# F3-Octo-Brushed-SIDE-USB-JMPR.net
KiCad netlist of a schematic drawn in EAGLE
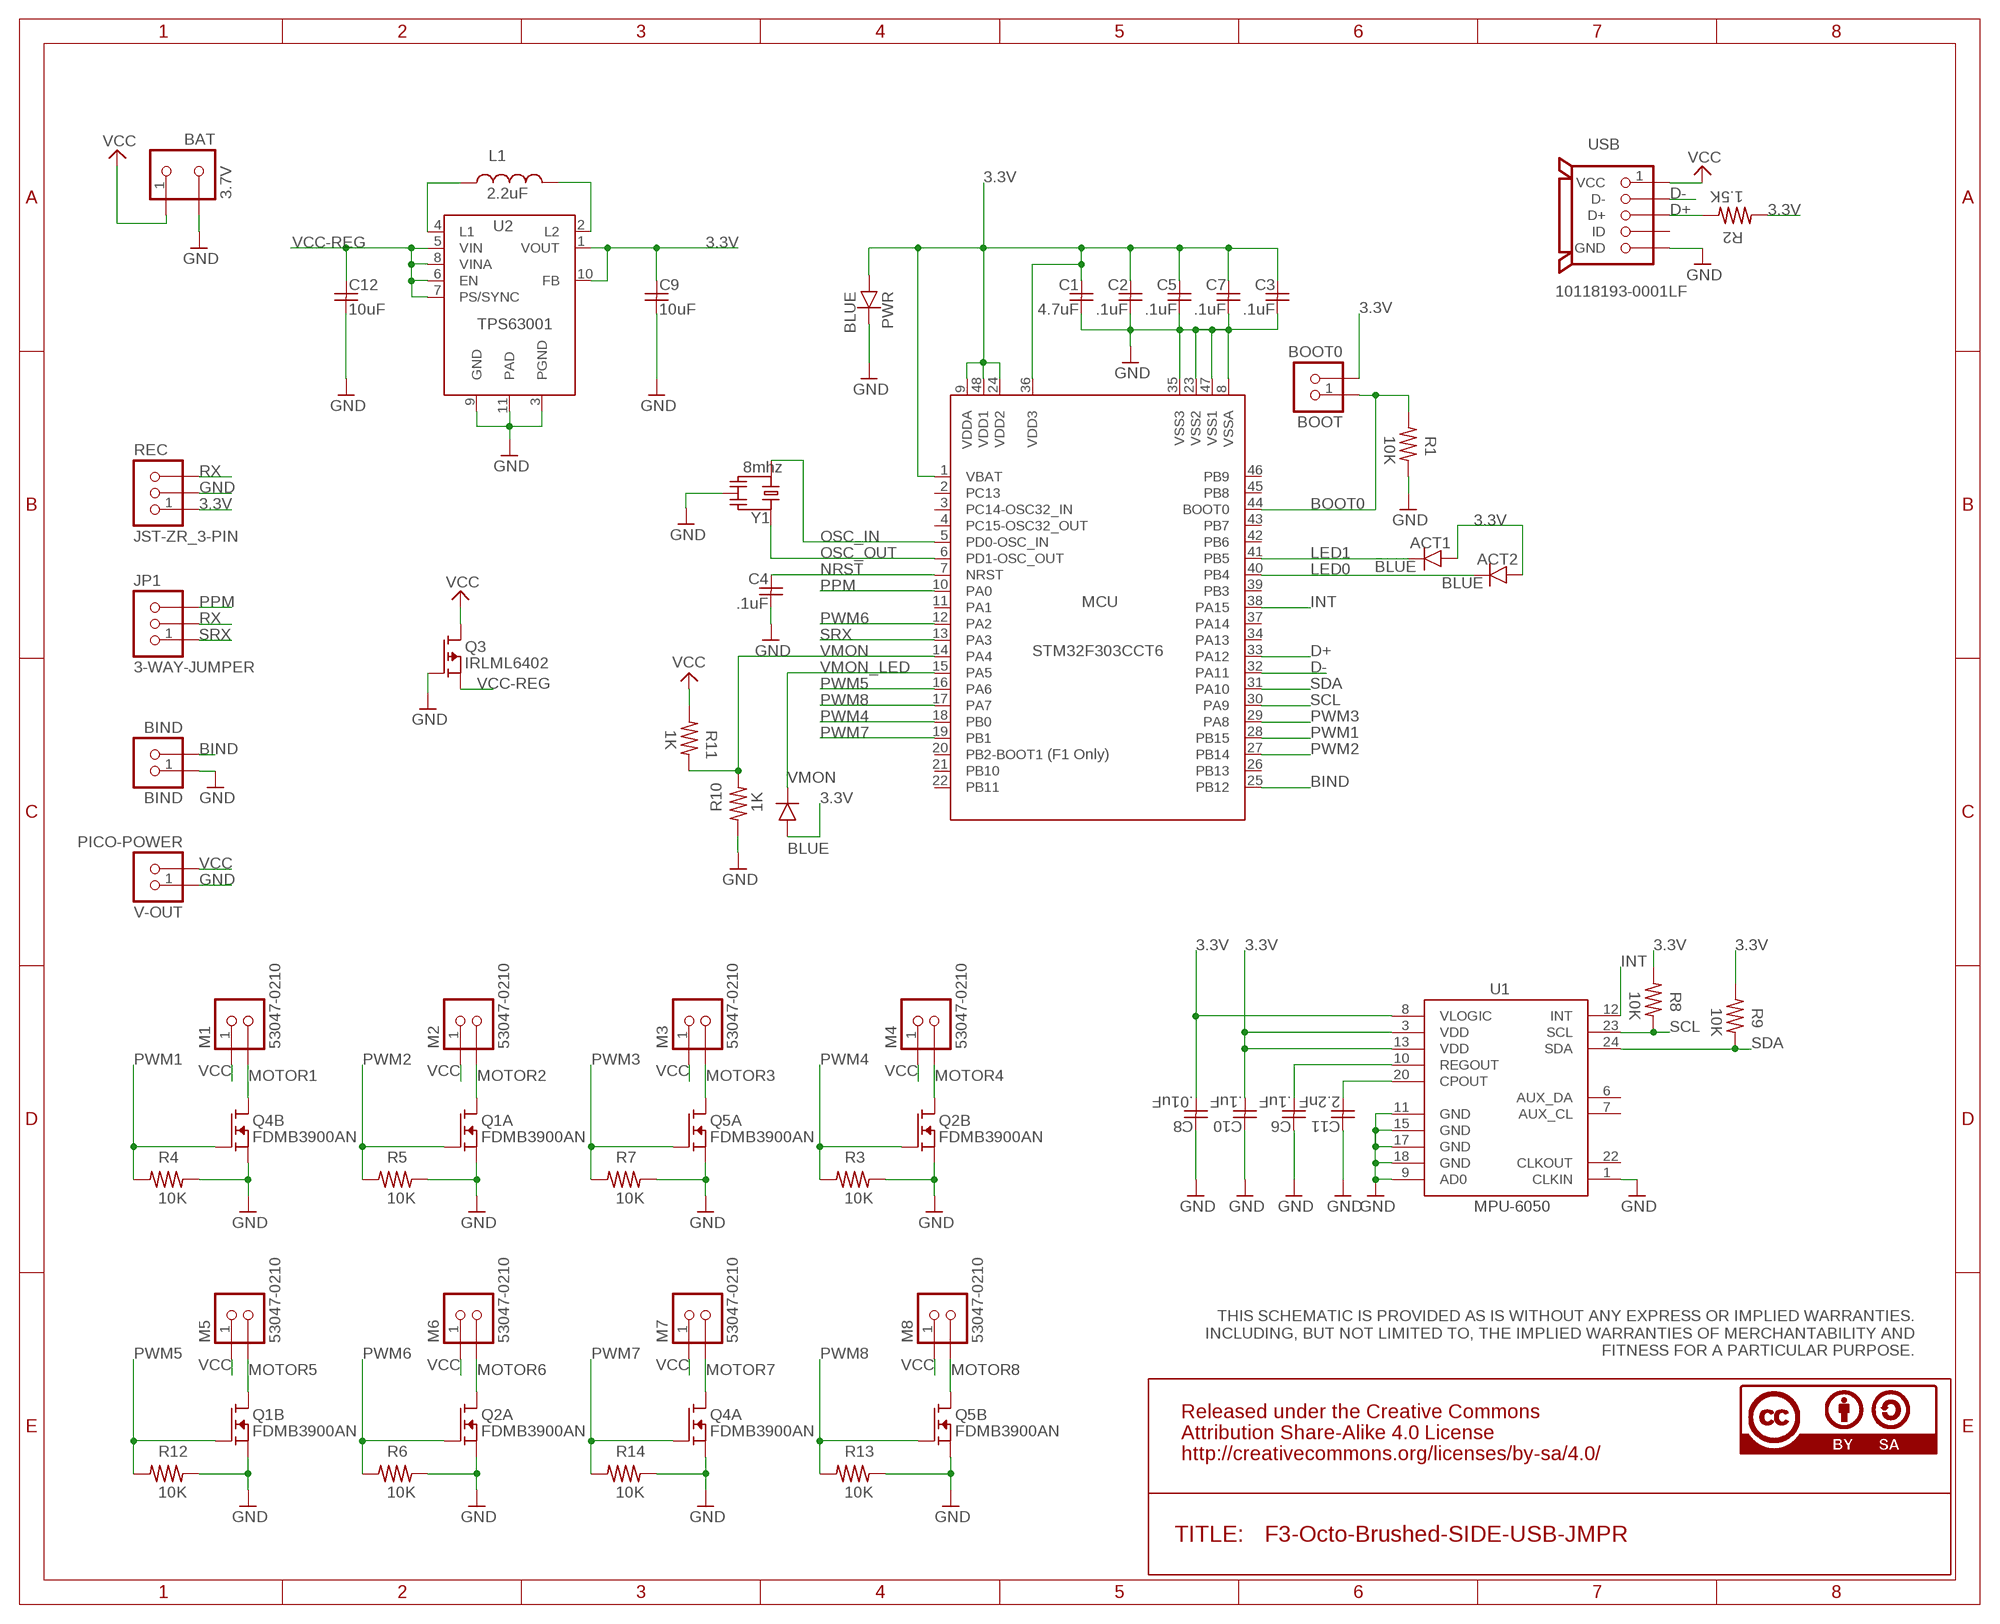
[diagram p0: schematic, sheet 1]

(export (version "E")
  (design (tool "Eeschema 10.0.6"))
  (components
    (comp (ref "ACT1")
      (value "BLUE")
      (footprint "eagle-import:SMD-CHIP-LED-0805")
      (fields (field (name "MF") "Kingbright") (field (name "MPN") "APHCM2012QBC/D-F01"))
      (libsource (lib "eagle-import") (part "SMD-CHIP-LED-0805"))
    )
    (comp (ref "ACT2")
      (value "BLUE")
      (footprint "eagle-import:SMD-CHIP-LED-0805")
      (fields (field (name "MF") "Kingbright") (field (name "MPN") "APHCM2012QBC/D-F01"))
      (libsource (lib "eagle-import") (part "SMD-CHIP-LED-0805"))
    )
    (comp (ref "BAT")
      (value "3.7V")
      (footprint "eagle-import:S2B-PH-K-S")
      (fields (field (name "MF") "JST") (field (name "MPN") "S2B-PH-K-S"))
      (libsource (lib "eagle-import") (part "JST-PH-BAT"))
    )
    (comp (ref "BIND")
      (value "BIND")
      (footprint "eagle-import:1.27MM-PINHEADX2")
      (fields (field (name "MF") "Sullins") (field (name "MPN") "GRPB021VWVN-RC (JUMPER IS M50-1930005)"))
      (libsource (lib "eagle-import") (part "1.27MM-PINHEADX2"))
    )
    (comp (ref "BOOT")
      (value "BOOT0")
      (footprint "eagle-import:1.27MM-PINHEADX2")
      (fields (field (name "MF") "Sullins") (field (name "MPN") "GRPB021VWVN-RC (JUMPER IS M50-1930005)"))
      (libsource (lib "eagle-import") (part "1.27MM-PINHEADX2"))
    )
    (comp (ref "C1")
      (value "4.7uF")
      (footprint "eagle-import:MUR-CAP-0603")
      (fields (field (name "MF") "Murata") (field (name "MPN") "GRJ188C70J475KE11D"))
      (libsource (lib "eagle-import") (part "CAPACITOR4.7UF"))
    )
    (comp (ref "C2")
      (value ".1uF")
      (footprint "eagle-import:MUR-CAP-0603")
      (fields (field (name "MF") "Murata") (field (name "MPN") "GRM188R71C104KA01D"))
      (libsource (lib "eagle-import") (part "CAPACITOR.1UF"))
    )
    (comp (ref "C3")
      (value ".1uF")
      (footprint "eagle-import:MUR-CAP-0603")
      (fields (field (name "MF") "Murata") (field (name "MPN") "GRM188R71C104KA01D"))
      (libsource (lib "eagle-import") (part "CAPACITOR.1UF"))
    )
    (comp (ref "C4")
      (value ".1uF")
      (footprint "eagle-import:MUR-CAP-0603")
      (fields (field (name "MF") "Murata") (field (name "MPN") "GRM188R71C104KA01D"))
      (libsource (lib "eagle-import") (part "CAPACITOR.1UF"))
    )
    (comp (ref "C5")
      (value ".1uF")
      (footprint "eagle-import:MUR-CAP-0603")
      (fields (field (name "MF") "Murata") (field (name "MPN") "GRM188R71C104KA01D"))
      (libsource (lib "eagle-import") (part "CAPACITOR.1UF"))
    )
    (comp (ref "C6")
      (value ".1uF")
      (footprint "eagle-import:MUR-CAP-0603")
      (fields (field (name "MF") "Murata") (field (name "MPN") "GRM188R71C104KA01D"))
      (libsource (lib "eagle-import") (part "CAPACITOR.1UF"))
    )
    (comp (ref "C7")
      (value ".1uF")
      (footprint "eagle-import:MUR-CAP-0603")
      (fields (field (name "MF") "Murata") (field (name "MPN") "GRM188R71C104KA01D"))
      (libsource (lib "eagle-import") (part "CAPACITOR.1UF"))
    )
    (comp (ref "C8")
      (value ".01uF")
      (footprint "eagle-import:MUR-CAP-0603")
      (fields (field (name "MF") "Murata") (field (name "MPN") "GRM188R71C103KA01D"))
      (libsource (lib "eagle-import") (part "CAPACITOR.01UF"))
    )
    (comp (ref "C9")
      (value "10uF")
      (footprint "eagle-import:YUDEN-CAP-0805")
      (fields (field (name "MF") "Taiyo Yuden") (field (name "MPN") "JMK212AB7106KG-T"))
      (libsource (lib "eagle-import") (part "CAPACITOR10UF"))
    )
    (comp (ref "C10")
      (value ".1uF")
      (footprint "eagle-import:MUR-CAP-0603")
      (fields (field (name "MF") "Murata") (field (name "MPN") "GRM188R71C104KA01D"))
      (libsource (lib "eagle-import") (part "CAPACITOR.1UF"))
    )
    (comp (ref "C11")
      (value "2.2nF")
      (footprint "eagle-import:MUR-CAP-0603")
      (fields (field (name "MF") "Murata") (field (name "MPN") "GRM188R71C222KA01D"))
      (libsource (lib "eagle-import") (part "CAPACITOR2.2NF"))
    )
    (comp (ref "C12")
      (value "10uF")
      (footprint "eagle-import:YUDEN-CAP-0805")
      (fields (field (name "MF") "Taiyo Yuden") (field (name "MPN") "JMK212AB7106KG-T"))
      (libsource (lib "eagle-import") (part "CAPACITOR10UF"))
    )
    (comp (ref "JP1")
      (value "3-WAY-JUMPER")
      (footprint "eagle-import:3-WAY-JUMPER")
      (libsource (lib "eagle-import") (part "3-WAY-JUMPER"))
    )
    (comp (ref "L1")
      (value "2.2uF")
      (footprint "eagle-import:NR301X")
      (fields (field (name "MF") "Taiyo Yuden") (field (name "MPN") "NR3015T2R2M"))
      (libsource (lib "eagle-import") (part "NR301X"))
    )
    (comp (ref "M1")
      (value "53047-0210")
      (footprint "eagle-import:PICO-53047-02")
      (fields (field (name "MF") "MOLEX"))
      (libsource (lib "eagle-import") (part "PICO-1.25-MOTOR"))
    )
    (comp (ref "M2")
      (value "53047-0210")
      (footprint "eagle-import:PICO-53047-02")
      (fields (field (name "MF") "MOLEX"))
      (libsource (lib "eagle-import") (part "PICO-1.25-MOTOR"))
    )
    (comp (ref "M3")
      (value "53047-0210")
      (footprint "eagle-import:PICO-53047-02")
      (fields (field (name "MF") "MOLEX"))
      (libsource (lib "eagle-import") (part "PICO-1.25-MOTOR"))
    )
    (comp (ref "M4")
      (value "53047-0210")
      (footprint "eagle-import:PICO-53047-02")
      (fields (field (name "MF") "MOLEX"))
      (libsource (lib "eagle-import") (part "PICO-1.25-MOTOR"))
    )
    (comp (ref "M5")
      (value "53047-0210")
      (footprint "eagle-import:PICO-53047-02")
      (fields (field (name "MF") "MOLEX"))
      (libsource (lib "eagle-import") (part "PICO-1.25-MOTOR"))
    )
    (comp (ref "M6")
      (value "53047-0210")
      (footprint "eagle-import:PICO-53047-02")
      (fields (field (name "MF") "MOLEX"))
      (libsource (lib "eagle-import") (part "PICO-1.25-MOTOR"))
    )
    (comp (ref "M7")
      (value "53047-0210")
      (footprint "eagle-import:PICO-53047-02")
      (fields (field (name "MF") "MOLEX"))
      (libsource (lib "eagle-import") (part "PICO-1.25-MOTOR"))
    )
    (comp (ref "M8")
      (value "53047-0210")
      (footprint "eagle-import:PICO-53047-02")
      (fields (field (name "MF") "MOLEX"))
      (libsource (lib "eagle-import") (part "PICO-1.25-MOTOR"))
    )
    (comp (ref "MCU")
      (value "STM32F303CCT6")
      (footprint "eagle-import:LQFP48-7X7")
      (fields (field (name "MF") "ST"))
      (libsource (lib "eagle-import") (part "STM32FX03-F3"))
    )
    (comp (ref "PWR")
      (value "BLUE")
      (footprint "eagle-import:SMD-CHIP-LED-0805")
      (fields (field (name "MF") "Kingbright") (field (name "MPN") "APHCM2012QBC/D-F01"))
      (libsource (lib "eagle-import") (part "SMD-CHIP-LED-0805"))
    )
    (comp (ref "Q1")
      (value "FDMB3900AN")
      (footprint "eagle-import:8-WDFN-DUAL")
      (fields (field (name "MF") "Fairchild"))
      (libsource (lib "eagle-import") (part "FDMB3900AN"))
    )
    (comp (ref "Q2")
      (value "FDMB3900AN")
      (footprint "eagle-import:8-WDFN-DUAL")
      (fields (field (name "MF") "Fairchild"))
      (libsource (lib "eagle-import") (part "FDMB3900AN"))
    )
    (comp (ref "Q3")
      (value "IRLML6402")
      (footprint "eagle-import:SOT-23")
      (fields (field (name "MF") "IR"))
      (libsource (lib "eagle-import") (part "IRLML6402"))
    )
    (comp (ref "Q4")
      (value "FDMB3900AN")
      (footprint "eagle-import:8-WDFN-DUAL")
      (fields (field (name "MF") "Fairchild"))
      (libsource (lib "eagle-import") (part "FDMB3900AN"))
    )
    (comp (ref "Q5")
      (value "FDMB3900AN")
      (footprint "eagle-import:8-WDFN-DUAL")
      (fields (field (name "MF") "Fairchild"))
      (libsource (lib "eagle-import") (part "FDMB3900AN"))
    )
    (comp (ref "R1")
      (value "10K")
      (footprint "eagle-import:VISH-RES-0603")
      (fields (field (name "MF") "Vishay") (field (name "MPN") "CRCW060310K0FKEAHP"))
      (libsource (lib "eagle-import") (part "RESISTOR10K"))
    )
    (comp (ref "R2")
      (value "1.5K")
      (footprint "eagle-import:VISH-RES-0603")
      (fields (field (name "MF") "Vishay") (field (name "MPN") "CRCW06031K50FKEAHP"))
      (libsource (lib "eagle-import") (part "RESISTOR1.5K"))
    )
    (comp (ref "R3")
      (value "10K")
      (footprint "eagle-import:VISH-RES-0603")
      (fields (field (name "MF") "Vishay") (field (name "MPN") "CRCW060310K0FKEAHP"))
      (libsource (lib "eagle-import") (part "RESISTOR10K"))
    )
    (comp (ref "R4")
      (value "10K")
      (footprint "eagle-import:VISH-RES-0603")
      (fields (field (name "MF") "Vishay") (field (name "MPN") "CRCW060310K0FKEAHP"))
      (libsource (lib "eagle-import") (part "RESISTOR10K"))
    )
    (comp (ref "R5")
      (value "10K")
      (footprint "eagle-import:VISH-RES-0603")
      (fields (field (name "MF") "Vishay") (field (name "MPN") "CRCW060310K0FKEAHP"))
      (libsource (lib "eagle-import") (part "RESISTOR10K"))
    )
    (comp (ref "R6")
      (value "10K")
      (footprint "eagle-import:VISH-RES-0603")
      (fields (field (name "MF") "Vishay") (field (name "MPN") "CRCW060310K0FKEAHP"))
      (libsource (lib "eagle-import") (part "RESISTOR10K"))
    )
    (comp (ref "R7")
      (value "10K")
      (footprint "eagle-import:VISH-RES-0603")
      (fields (field (name "MF") "Vishay") (field (name "MPN") "CRCW060310K0FKEAHP"))
      (libsource (lib "eagle-import") (part "RESISTOR10K"))
    )
    (comp (ref "R8")
      (value "10K")
      (footprint "eagle-import:VISH-RES-0603")
      (fields (field (name "MF") "Vishay") (field (name "MPN") "CRCW060310K0FKEAHP"))
      (libsource (lib "eagle-import") (part "RESISTOR10K"))
    )
    (comp (ref "R9")
      (value "10K")
      (footprint "eagle-import:VISH-RES-0603")
      (fields (field (name "MF") "Vishay") (field (name "MPN") "CRCW060310K0FKEAHP"))
      (libsource (lib "eagle-import") (part "RESISTOR10K"))
    )
    (comp (ref "R10")
      (value "1K")
      (footprint "eagle-import:VISH-RES-0603")
      (fields (field (name "MF") "Vishay") (field (name "MPN") "CRCW06031K00FKEAHP"))
      (libsource (lib "eagle-import") (part "RESISTOR1K"))
    )
    (comp (ref "R11")
      (value "1K")
      (footprint "eagle-import:VISH-RES-0603")
      (fields (field (name "MF") "Vishay") (field (name "MPN") "CRCW06031K00FKEAHP"))
      (libsource (lib "eagle-import") (part "RESISTOR1K"))
    )
    (comp (ref "R12")
      (value "10K")
      (footprint "eagle-import:VISH-RES-0603")
      (fields (field (name "MF") "Vishay") (field (name "MPN") "CRCW060310K0FKEAHP"))
      (libsource (lib "eagle-import") (part "RESISTOR10K"))
    )
    (comp (ref "R13")
      (value "10K")
      (footprint "eagle-import:VISH-RES-0603")
      (fields (field (name "MF") "Vishay") (field (name "MPN") "CRCW060310K0FKEAHP"))
      (libsource (lib "eagle-import") (part "RESISTOR10K"))
    )
    (comp (ref "R14")
      (value "10K")
      (footprint "eagle-import:VISH-RES-0603")
      (fields (field (name "MF") "Vishay") (field (name "MPN") "CRCW060310K0FKEAHP"))
      (libsource (lib "eagle-import") (part "RESISTOR10K"))
    )
    (comp (ref "REC")
      (value "JST-ZR_3-PIN")
      (footprint "eagle-import:S3B-ZR")
      (fields (field (name "MF") "JST") (field (name "MPN") "S3B-ZR"))
      (libsource (lib "eagle-import") (part "JST-ZR_3-PIN"))
    )
    (comp (ref "U1")
      (value "MPU-6050")
      (footprint "eagle-import:QFN24-4X4")
      (fields (field (name "MF") "Invensense"))
      (libsource (lib "eagle-import") (part "MPU-6050"))
    )
    (comp (ref "U2")
      (value "TPS63001")
      (footprint "eagle-import:VSON-N10")
      (fields (field (name "MF") "TI") (field (name "MPN") "TPS63001DRCR"))
      (libsource (lib "eagle-import") (part "TPS630XX-TPS63001"))
    )
    (comp (ref "USB")
      (value "10118193-0001LF")
      (footprint "eagle-import:10118193-0001LF")
      (fields (field (name "MF") "FCI"))
      (libsource (lib "eagle-import") (part "USB-MICRO-B-FCI"))
    )
    (comp (ref "V-OUT")
      (value "PICO-POWER")
      (footprint "eagle-import:PICO_1.25_.5MM")
      (fields (field (name "MF") "Molex") (field (name "MPN") "53047-0210"))
      (libsource (lib "eagle-import") (part "PICO-POWER"))
    )
    (comp (ref "VMON")
      (value "BLUE")
      (footprint "eagle-import:SMD-CHIP-LED-0805")
      (fields (field (name "MF") "Kingbright") (field (name "MPN") "APHCM2012QBC/D-F01"))
      (libsource (lib "eagle-import") (part "SMD-CHIP-LED-0805"))
    )
    (comp (ref "Y1")
      (value "8mhz")
      (footprint "eagle-import:RESONATOR_8")
      (fields (field (name "MF") "Murata") (field (name "MPN") "CSTCE8M00G55-R0"))
      (libsource (lib "eagle-import") (part "RESONATOR8MHZ"))
    )
  )
  (nets
    (net (code "1") (name "/3.3V") (class "Default")
      (node (ref "ACT1") (pin "A") (pinfunction "A_A") (pintype "passive"))
      (node (ref "ACT2") (pin "A") (pinfunction "A_A") (pintype "passive"))
      (node (ref "BOOT") (pin "2") (pinfunction "2_2") (pintype "passive"))
      (node (ref "C1") (pin "1") (pinfunction "1_1") (pintype "passive"))
      (node (ref "C10") (pin "2") (pinfunction "2_2") (pintype "passive"))
      (node (ref "C2") (pin "1") (pinfunction "1_1") (pintype "passive"))
      (node (ref "C3") (pin "1") (pinfunction "1_1") (pintype "passive"))
      (node (ref "C5") (pin "1") (pinfunction "1_1") (pintype "passive"))
      (node (ref "C7") (pin "1") (pinfunction "1_1") (pintype "passive"))
      (node (ref "C8") (pin "2") (pinfunction "2_2") (pintype "passive"))
      (node (ref "C9") (pin "1") (pinfunction "1_1") (pintype "passive"))
      (node (ref "MCU") (pin "1") (pinfunction "VBAT_1") (pintype "bidirectional"))
      (node (ref "MCU") (pin "24") (pinfunction "VDD2_24") (pintype "bidirectional"))
      (node (ref "MCU") (pin "36") (pinfunction "VDD3_36") (pintype "bidirectional"))
      (node (ref "MCU") (pin "48") (pinfunction "VDD1_48") (pintype "bidirectional"))
      (node (ref "MCU") (pin "9") (pinfunction "VDDA_9") (pintype "bidirectional"))
      (node (ref "PWR") (pin "A") (pinfunction "A_A") (pintype "passive"))
      (node (ref "R2") (pin "2") (pinfunction "2_2") (pintype "passive"))
      (node (ref "R8") (pin "2") (pinfunction "2_2") (pintype "passive"))
      (node (ref "R9") (pin "2") (pinfunction "2_2") (pintype "passive"))
      (node (ref "REC") (pin "1") (pinfunction "1_1") (pintype "bidirectional"))
      (node (ref "U1") (pin "13") (pinfunction "VDD_13") (pintype "bidirectional"))
      (node (ref "U1") (pin "3") (pinfunction "VDD_3") (pintype "bidirectional"))
      (node (ref "U1") (pin "8") (pinfunction "VLOGIC_8") (pintype "bidirectional"))
      (node (ref "U2") (pin "1") (pinfunction "VOUT_1") (pintype "bidirectional"))
      (node (ref "U2") (pin "10") (pinfunction "FB_10") (pintype "bidirectional"))
      (node (ref "VMON") (pin "A") (pinfunction "A_A") (pintype "passive"))
    )
    (net (code "2") (name "/BIND") (class "Default")
      (node (ref "BIND") (pin "2") (pinfunction "2_2") (pintype "passive"))
      (node (ref "MCU") (pin "25") (pinfunction "PB12_25") (pintype "bidirectional"))
    )
    (net (code "3") (name "/BOOT0") (class "Default")
      (node (ref "BOOT") (pin "1") (pinfunction "1_1") (pintype "passive"))
      (node (ref "MCU") (pin "44") (pinfunction "BOOT0_44") (pintype "bidirectional"))
      (node (ref "R1") (pin "2") (pinfunction "2_2") (pintype "passive"))
    )
    (net (code "4") (name "/D+") (class "Default")
      (node (ref "MCU") (pin "33") (pinfunction "PA12_33") (pintype "bidirectional"))
      (node (ref "R2") (pin "1") (pinfunction "1_1") (pintype "passive"))
      (node (ref "USB") (pin "3") (pinfunction "D+_3") (pintype "passive"))
    )
    (net (code "5") (name "/D-") (class "Default")
      (node (ref "MCU") (pin "32") (pinfunction "PA11_32") (pintype "bidirectional"))
      (node (ref "USB") (pin "2") (pinfunction "D-_2") (pintype "passive"))
    )
    (net (code "6") (name "/INT") (class "Default")
      (node (ref "MCU") (pin "38") (pinfunction "PA15_38") (pintype "bidirectional"))
      (node (ref "U1") (pin "12") (pinfunction "INT_12") (pintype "bidirectional"))
    )
    (net (code "7") (name "/LED0") (class "Default")
      (node (ref "ACT2") (pin "C") (pinfunction "C_C") (pintype "passive"))
      (node (ref "MCU") (pin "40") (pinfunction "PB4_40") (pintype "bidirectional"))
    )
    (net (code "8") (name "/LED1") (class "Default")
      (node (ref "ACT1") (pin "C") (pinfunction "C_C") (pintype "passive"))
      (node (ref "MCU") (pin "41") (pinfunction "PB5_41") (pintype "bidirectional"))
    )
    (net (code "9") (name "/MOTOR1") (class "Default")
      (node (ref "M1") (pin "2") (pinfunction "2_2") (pintype "passive"))
      (node (ref "Q4") (pin "5+6") (pinfunction "D_5+6") (pintype "bidirectional"))
    )
    (net (code "10") (name "/MOTOR2") (class "Default")
      (node (ref "M2") (pin "2") (pinfunction "2_2") (pintype "passive"))
      (node (ref "Q1") (pin "7+8") (pinfunction "D_7+8") (pintype "bidirectional"))
    )
    (net (code "11") (name "/MOTOR3") (class "Default")
      (node (ref "M3") (pin "2") (pinfunction "2_2") (pintype "passive"))
      (node (ref "Q5") (pin "7+8") (pinfunction "D_7+8") (pintype "bidirectional"))
    )
    (net (code "12") (name "/MOTOR4") (class "Default")
      (node (ref "M4") (pin "2") (pinfunction "2_2") (pintype "passive"))
      (node (ref "Q2") (pin "5+6") (pinfunction "D_5+6") (pintype "bidirectional"))
    )
    (net (code "13") (name "/MOTOR5") (class "Default")
      (node (ref "M5") (pin "2") (pinfunction "2_2") (pintype "passive"))
      (node (ref "Q1") (pin "5+6") (pinfunction "D_5+6") (pintype "bidirectional"))
    )
    (net (code "14") (name "/MOTOR6") (class "Default")
      (node (ref "M6") (pin "2") (pinfunction "2_2") (pintype "passive"))
      (node (ref "Q2") (pin "7+8") (pinfunction "D_7+8") (pintype "bidirectional"))
    )
    (net (code "15") (name "/MOTOR7") (class "Default")
      (node (ref "M7") (pin "2") (pinfunction "2_2") (pintype "passive"))
      (node (ref "Q4") (pin "7+8") (pinfunction "D_7+8") (pintype "bidirectional"))
    )
    (net (code "16") (name "/MOTOR8") (class "Default")
      (node (ref "M8") (pin "2") (pinfunction "2_2") (pintype "passive"))
      (node (ref "Q5") (pin "5+6") (pinfunction "D_5+6") (pintype "bidirectional"))
    )
    (net (code "17") (name "/NRST") (class "Default")
      (node (ref "C4") (pin "1") (pinfunction "1_1") (pintype "passive"))
      (node (ref "MCU") (pin "7") (pinfunction "NRST_7") (pintype "bidirectional"))
    )
    (net (code "18") (name "/OSC_IN") (class "Default")
      (node (ref "MCU") (pin "5") (pinfunction "PD0-OSC_IN_5") (pintype "bidirectional"))
      (node (ref "Y1") (pin "3") (pinfunction "3_3") (pintype "passive"))
    )
    (net (code "19") (name "/OSC_OUT") (class "Default")
      (node (ref "MCU") (pin "6") (pinfunction "PD1-OSC_OUT_6") (pintype "bidirectional"))
      (node (ref "Y1") (pin "1") (pinfunction "1_1") (pintype "passive"))
    )
    (net (code "20") (name "/PPM") (class "Default")
      (node (ref "JP1") (pin "3") (pinfunction "3_3") (pintype "bidirectional"))
      (node (ref "MCU") (pin "10") (pinfunction "PA0_10") (pintype "bidirectional"))
    )
    (net (code "21") (name "/PWM1") (class "Default")
      (node (ref "MCU") (pin "28") (pinfunction "PB15_28") (pintype "bidirectional"))
      (node (ref "Q4") (pin "4@G2") (pinfunction "G_4@G2") (pintype "bidirectional"))
      (node (ref "R4") (pin "2") (pinfunction "2_2") (pintype "passive"))
    )
    (net (code "22") (name "/PWM2") (class "Default")
      (node (ref "MCU") (pin "27") (pinfunction "PB14_27") (pintype "bidirectional"))
      (node (ref "Q1") (pin "2@G1") (pinfunction "G_2@G1") (pintype "bidirectional"))
      (node (ref "R5") (pin "2") (pinfunction "2_2") (pintype "passive"))
    )
    (net (code "23") (name "/PWM3") (class "Default")
      (node (ref "MCU") (pin "29") (pinfunction "PA8_29") (pintype "bidirectional"))
      (node (ref "Q5") (pin "2@G1") (pinfunction "G_2@G1") (pintype "bidirectional"))
      (node (ref "R7") (pin "2") (pinfunction "2_2") (pintype "passive"))
    )
    (net (code "24") (name "/PWM4") (class "Default")
      (node (ref "MCU") (pin "18") (pinfunction "PB0_18") (pintype "bidirectional"))
      (node (ref "Q2") (pin "4@G2") (pinfunction "G_4@G2") (pintype "bidirectional"))
      (node (ref "R3") (pin "2") (pinfunction "2_2") (pintype "passive"))
    )
    (net (code "25") (name "/PWM5") (class "Default")
      (node (ref "MCU") (pin "16") (pinfunction "PA6_16") (pintype "bidirectional"))
      (node (ref "Q1") (pin "4@G2") (pinfunction "G_4@G2") (pintype "bidirectional"))
      (node (ref "R12") (pin "2") (pinfunction "2_2") (pintype "passive"))
    )
    (net (code "26") (name "/PWM6") (class "Default")
      (node (ref "MCU") (pin "12") (pinfunction "PA2_12") (pintype "bidirectional"))
      (node (ref "Q2") (pin "2@G1") (pinfunction "G_2@G1") (pintype "bidirectional"))
      (node (ref "R6") (pin "2") (pinfunction "2_2") (pintype "passive"))
    )
    (net (code "27") (name "/PWM7") (class "Default")
      (node (ref "MCU") (pin "19") (pinfunction "PB1_19") (pintype "bidirectional"))
      (node (ref "Q4") (pin "2@G1") (pinfunction "G_2@G1") (pintype "bidirectional"))
      (node (ref "R14") (pin "2") (pinfunction "2_2") (pintype "passive"))
    )
    (net (code "28") (name "/PWM8") (class "Default")
      (node (ref "MCU") (pin "17") (pinfunction "PA7_17") (pintype "bidirectional"))
      (node (ref "Q5") (pin "4@G2") (pinfunction "G_4@G2") (pintype "bidirectional"))
      (node (ref "R13") (pin "2") (pinfunction "2_2") (pintype "passive"))
    )
    (net (code "29") (name "/RX") (class "Default")
      (node (ref "JP1") (pin "2") (pinfunction "2_2") (pintype "bidirectional"))
      (node (ref "REC") (pin "3") (pinfunction "3_3") (pintype "bidirectional"))
    )
    (net (code "30") (name "/SCL") (class "Default")
      (node (ref "MCU") (pin "30") (pinfunction "PA9_30") (pintype "bidirectional"))
      (node (ref "R8") (pin "1") (pinfunction "1_1") (pintype "passive"))
      (node (ref "U1") (pin "23") (pinfunction "SCL_23") (pintype "bidirectional"))
    )
    (net (code "31") (name "/SDA") (class "Default")
      (node (ref "MCU") (pin "31") (pinfunction "PA10_31") (pintype "bidirectional"))
      (node (ref "R9") (pin "1") (pinfunction "1_1") (pintype "passive"))
      (node (ref "U1") (pin "24") (pinfunction "SDA_24") (pintype "bidirectional"))
    )
    (net (code "32") (name "/SRX") (class "Default")
      (node (ref "JP1") (pin "1") (pinfunction "1_1") (pintype "bidirectional"))
      (node (ref "MCU") (pin "13") (pinfunction "PA3_13") (pintype "bidirectional"))
    )
    (net (code "33") (name "/VCC-REG") (class "Default")
      (node (ref "C12") (pin "1") (pinfunction "1_1") (pintype "passive"))
      (node (ref "Q3") (pin "2") (pinfunction "S_2") (pintype "bidirectional"))
      (node (ref "U2") (pin "5") (pinfunction "VIN_5") (pintype "bidirectional"))
      (node (ref "U2") (pin "6") (pinfunction "EN_6") (pintype "bidirectional"))
      (node (ref "U2") (pin "7") (pinfunction "PS/SYNC_7") (pintype "bidirectional"))
      (node (ref "U2") (pin "8") (pinfunction "VINA_8") (pintype "bidirectional"))
    )
    (net (code "34") (name "/VMON") (class "Default")
      (node (ref "MCU") (pin "14") (pinfunction "PA4_14") (pintype "bidirectional"))
      (node (ref "R10") (pin "1") (pinfunction "1_1") (pintype "passive"))
      (node (ref "R11") (pin "1") (pinfunction "1_1") (pintype "passive"))
    )
    (net (code "35") (name "/VMON_LED") (class "Default")
      (node (ref "MCU") (pin "15") (pinfunction "PA5_15") (pintype "bidirectional"))
      (node (ref "VMON") (pin "C") (pinfunction "C_C") (pintype "passive"))
    )
    (net (code "36") (name "GND") (class "Default")
      (node (ref "BAT") (pin "2") (pinfunction "2_2") (pintype "bidirectional"))
      (node (ref "BIND") (pin "1") (pinfunction "1_1") (pintype "passive"))
      (node (ref "C1") (pin "2") (pinfunction "2_2") (pintype "passive"))
      (node (ref "C10") (pin "1") (pinfunction "1_1") (pintype "passive"))
      (node (ref "C11") (pin "1") (pinfunction "1_1") (pintype "passive"))
      (node (ref "C12") (pin "2") (pinfunction "2_2") (pintype "passive"))
      (node (ref "C2") (pin "2") (pinfunction "2_2") (pintype "passive"))
      (node (ref "C3") (pin "2") (pinfunction "2_2") (pintype "passive"))
      (node (ref "C4") (pin "2") (pinfunction "2_2") (pintype "passive"))
      (node (ref "C5") (pin "2") (pinfunction "2_2") (pintype "passive"))
      (node (ref "C6") (pin "1") (pinfunction "1_1") (pintype "passive"))
      (node (ref "C7") (pin "2") (pinfunction "2_2") (pintype "passive"))
      (node (ref "C8") (pin "1") (pinfunction "1_1") (pintype "passive"))
      (node (ref "C9") (pin "2") (pinfunction "2_2") (pintype "passive"))
      (node (ref "MCU") (pin "23") (pinfunction "VSS2_23") (pintype "bidirectional"))
      (node (ref "MCU") (pin "35") (pinfunction "VSS3_35") (pintype "bidirectional"))
      (node (ref "MCU") (pin "47") (pinfunction "VSS1_47") (pintype "bidirectional"))
      (node (ref "MCU") (pin "8") (pinfunction "VSSA_8") (pintype "bidirectional"))
      (node (ref "PWR") (pin "C") (pinfunction "C_C") (pintype "passive"))
      (node (ref "Q1") (pin "1@S1") (pinfunction "S_1@S1") (pintype "bidirectional"))
      (node (ref "Q1") (pin "3@S1") (pinfunction "S_3@S1") (pintype "bidirectional"))
      (node (ref "Q2") (pin "1@S1") (pinfunction "S_1@S1") (pintype "bidirectional"))
      (node (ref "Q2") (pin "3@S1") (pinfunction "S_3@S1") (pintype "bidirectional"))
      (node (ref "Q3") (pin "1") (pinfunction "G_1") (pintype "bidirectional"))
      (node (ref "Q4") (pin "1@S1") (pinfunction "S_1@S1") (pintype "bidirectional"))
      (node (ref "Q4") (pin "3@S1") (pinfunction "S_3@S1") (pintype "bidirectional"))
      (node (ref "Q5") (pin "1@S1") (pinfunction "S_1@S1") (pintype "bidirectional"))
      (node (ref "Q5") (pin "3@S1") (pinfunction "S_3@S1") (pintype "bidirectional"))
      (node (ref "R1") (pin "1") (pinfunction "1_1") (pintype "passive"))
      (node (ref "R10") (pin "2") (pinfunction "2_2") (pintype "passive"))
      (node (ref "R12") (pin "1") (pinfunction "1_1") (pintype "passive"))
      (node (ref "R13") (pin "1") (pinfunction "1_1") (pintype "passive"))
      (node (ref "R14") (pin "1") (pinfunction "1_1") (pintype "passive"))
      (node (ref "R3") (pin "1") (pinfunction "1_1") (pintype "passive"))
      (node (ref "R4") (pin "1") (pinfunction "1_1") (pintype "passive"))
      (node (ref "R5") (pin "1") (pinfunction "1_1") (pintype "passive"))
      (node (ref "R6") (pin "1") (pinfunction "1_1") (pintype "passive"))
      (node (ref "R7") (pin "1") (pinfunction "1_1") (pintype "passive"))
      (node (ref "REC") (pin "2") (pinfunction "2_2") (pintype "bidirectional"))
      (node (ref "U1") (pin "1") (pinfunction "CLKIN_1") (pintype "bidirectional"))
      (node (ref "U1") (pin "11") (pinfunction "GND_11") (pintype "bidirectional"))
      (node (ref "U1") (pin "15") (pinfunction "GND_15") (pintype "bidirectional"))
      (node (ref "U1") (pin "17") (pinfunction "GND_17") (pintype "bidirectional"))
      (node (ref "U1") (pin "18") (pinfunction "GND_18") (pintype "bidirectional"))
      (node (ref "U1") (pin "9") (pinfunction "AD0_9") (pintype "bidirectional"))
      (node (ref "U2") (pin "11") (pinfunction "PAD_11") (pintype "bidirectional"))
      (node (ref "U2") (pin "3") (pinfunction "PGND_3") (pintype "bidirectional"))
      (node (ref "U2") (pin "9") (pinfunction "GND_9") (pintype "bidirectional"))
      (node (ref "USB") (pin "5") (pinfunction "GND_5") (pintype "passive"))
      (node (ref "USB") (pin "GND") (pinfunction "GND_GND") (pintype "passive"))
      (node (ref "USB") (pin "GND2") (pinfunction "GND_GND2") (pintype "passive"))
      (node (ref "USB") (pin "HOLE1") (pinfunction "GND_HOLE1") (pintype "passive"))
      (node (ref "USB") (pin "HOLE2") (pinfunction "GND_HOLE2") (pintype "passive"))
      (node (ref "V-OUT") (pin "1") (pinfunction "1_1") (pintype "passive"))
      (node (ref "Y1") (pin "2") (pinfunction "2_2") (pintype "passive"))
    )
    (net (code "37") (name "Net-(U1-CPOUT)") (class "Default")
      (node (ref "C11") (pin "2") (pinfunction "2_2") (pintype "passive"))
      (node (ref "U1") (pin "20") (pinfunction "CPOUT_20") (pintype "bidirectional"))
    )
    (net (code "38") (name "Net-(U1-REGOUT)") (class "Default")
      (node (ref "C6") (pin "2") (pinfunction "2_2") (pintype "passive"))
      (node (ref "U1") (pin "10") (pinfunction "REGOUT_10") (pintype "bidirectional"))
    )
    (net (code "39") (name "Net-(U2-L1)") (class "Default")
      (node (ref "L1") (pin "1") (pinfunction "1_1") (pintype "passive"))
      (node (ref "U2") (pin "4") (pinfunction "L1_4") (pintype "bidirectional"))
    )
    (net (code "40") (name "Net-(U2-L2)") (class "Default")
      (node (ref "L1") (pin "2") (pinfunction "2_2") (pintype "passive"))
      (node (ref "U2") (pin "2") (pinfunction "L2_2") (pintype "bidirectional"))
    )
    (net (code "41") (name "VCC") (class "Default")
      (node (ref "BAT") (pin "1") (pinfunction "1_1") (pintype "bidirectional"))
      (node (ref "M1") (pin "1") (pinfunction "1_1") (pintype "passive"))
      (node (ref "M2") (pin "1") (pinfunction "1_1") (pintype "passive"))
      (node (ref "M3") (pin "1") (pinfunction "1_1") (pintype "passive"))
      (node (ref "M4") (pin "1") (pinfunction "1_1") (pintype "passive"))
      (node (ref "M5") (pin "1") (pinfunction "1_1") (pintype "passive"))
      (node (ref "M6") (pin "1") (pinfunction "1_1") (pintype "passive"))
      (node (ref "M7") (pin "1") (pinfunction "1_1") (pintype "passive"))
      (node (ref "M8") (pin "1") (pinfunction "1_1") (pintype "passive"))
      (node (ref "Q3") (pin "3") (pinfunction "D_3") (pintype "bidirectional"))
      (node (ref "R11") (pin "2") (pinfunction "2_2") (pintype "passive"))
      (node (ref "USB") (pin "1") (pinfunction "VCC_1") (pintype "passive"))
      (node (ref "V-OUT") (pin "2") (pinfunction "2_2") (pintype "passive"))
    )
    (net (code "42") (name "unconnected-(MCU-PA1-Pad11)") (class "Default")
      (node (ref "MCU") (pin "11") (pinfunction "PA1_11") (pintype "bidirectional"))
    )
    (net (code "43") (name "unconnected-(MCU-PA13-Pad34)") (class "Default")
      (node (ref "MCU") (pin "34") (pinfunction "PA13_34") (pintype "bidirectional"))
    )
    (net (code "44") (name "unconnected-(MCU-PA14-Pad37)") (class "Default")
      (node (ref "MCU") (pin "37") (pinfunction "PA14_37") (pintype "bidirectional"))
    )
    (net (code "45") (name "unconnected-(MCU-PB2-BOOT1-Pad20)") (class "Default")
      (node (ref "MCU") (pin "20") (pinfunction "PB2-BOOT1_20") (pintype "bidirectional"))
    )
    (net (code "46") (name "unconnected-(MCU-PB3-Pad39)") (class "Default")
      (node (ref "MCU") (pin "39") (pinfunction "PB3_39") (pintype "bidirectional"))
    )
    (net (code "47") (name "unconnected-(MCU-PB6-Pad42)") (class "Default")
      (node (ref "MCU") (pin "42") (pinfunction "PB6_42") (pintype "bidirectional"))
    )
    (net (code "48") (name "unconnected-(MCU-PB7-Pad43)") (class "Default")
      (node (ref "MCU") (pin "43") (pinfunction "PB7_43") (pintype "bidirectional"))
    )
    (net (code "49") (name "unconnected-(MCU-PB8-Pad45)") (class "Default")
      (node (ref "MCU") (pin "45") (pinfunction "PB8_45") (pintype "bidirectional"))
    )
    (net (code "50") (name "unconnected-(MCU-PB9-Pad46)") (class "Default")
      (node (ref "MCU") (pin "46") (pinfunction "PB9_46") (pintype "bidirectional"))
    )
    (net (code "51") (name "unconnected-(MCU-PB10-Pad21)") (class "Default")
      (node (ref "MCU") (pin "21") (pinfunction "PB10_21") (pintype "bidirectional"))
    )
    (net (code "52") (name "unconnected-(MCU-PB11-Pad22)") (class "Default")
      (node (ref "MCU") (pin "22") (pinfunction "PB11_22") (pintype "bidirectional"))
    )
    (net (code "53") (name "unconnected-(MCU-PB13-Pad26)") (class "Default")
      (node (ref "MCU") (pin "26") (pinfunction "PB13_26") (pintype "bidirectional"))
    )
    (net (code "54") (name "unconnected-(MCU-PC13-Pad2)") (class "Default")
      (node (ref "MCU") (pin "2") (pinfunction "PC13_2") (pintype "bidirectional"))
    )
    (net (code "55") (name "unconnected-(MCU-PC14-OSC32_IN-Pad3)") (class "Default")
      (node (ref "MCU") (pin "3") (pinfunction "PC14-OSC32_IN_3") (pintype "bidirectional"))
    )
    (net (code "56") (name "unconnected-(MCU-PC15-OSC32_OUT-Pad4)") (class "Default")
      (node (ref "MCU") (pin "4") (pinfunction "PC15-OSC32_OUT_4") (pintype "bidirectional"))
    )
    (net (code "57") (name "unconnected-(U1-AUX_CL-Pad7)") (class "Default")
      (node (ref "U1") (pin "7") (pinfunction "AUX_CL_7") (pintype "bidirectional"))
    )
    (net (code "58") (name "unconnected-(U1-AUX_DA-Pad6)") (class "Default")
      (node (ref "U1") (pin "6") (pinfunction "AUX_DA_6") (pintype "bidirectional"))
    )
    (net (code "59") (name "unconnected-(U1-CLKOUT-Pad22)") (class "Default")
      (node (ref "U1") (pin "22") (pinfunction "CLKOUT_22") (pintype "bidirectional"))
    )
    (net (code "60") (name "unconnected-(USB-ID-Pad4)") (class "Default")
      (node (ref "USB") (pin "4") (pinfunction "ID_4") (pintype "passive"))
    )
  )
)
